# ProDoc_Board2_2025-10-18.net
KiCad netlist of a schematic drawn in EasyEDA Pro
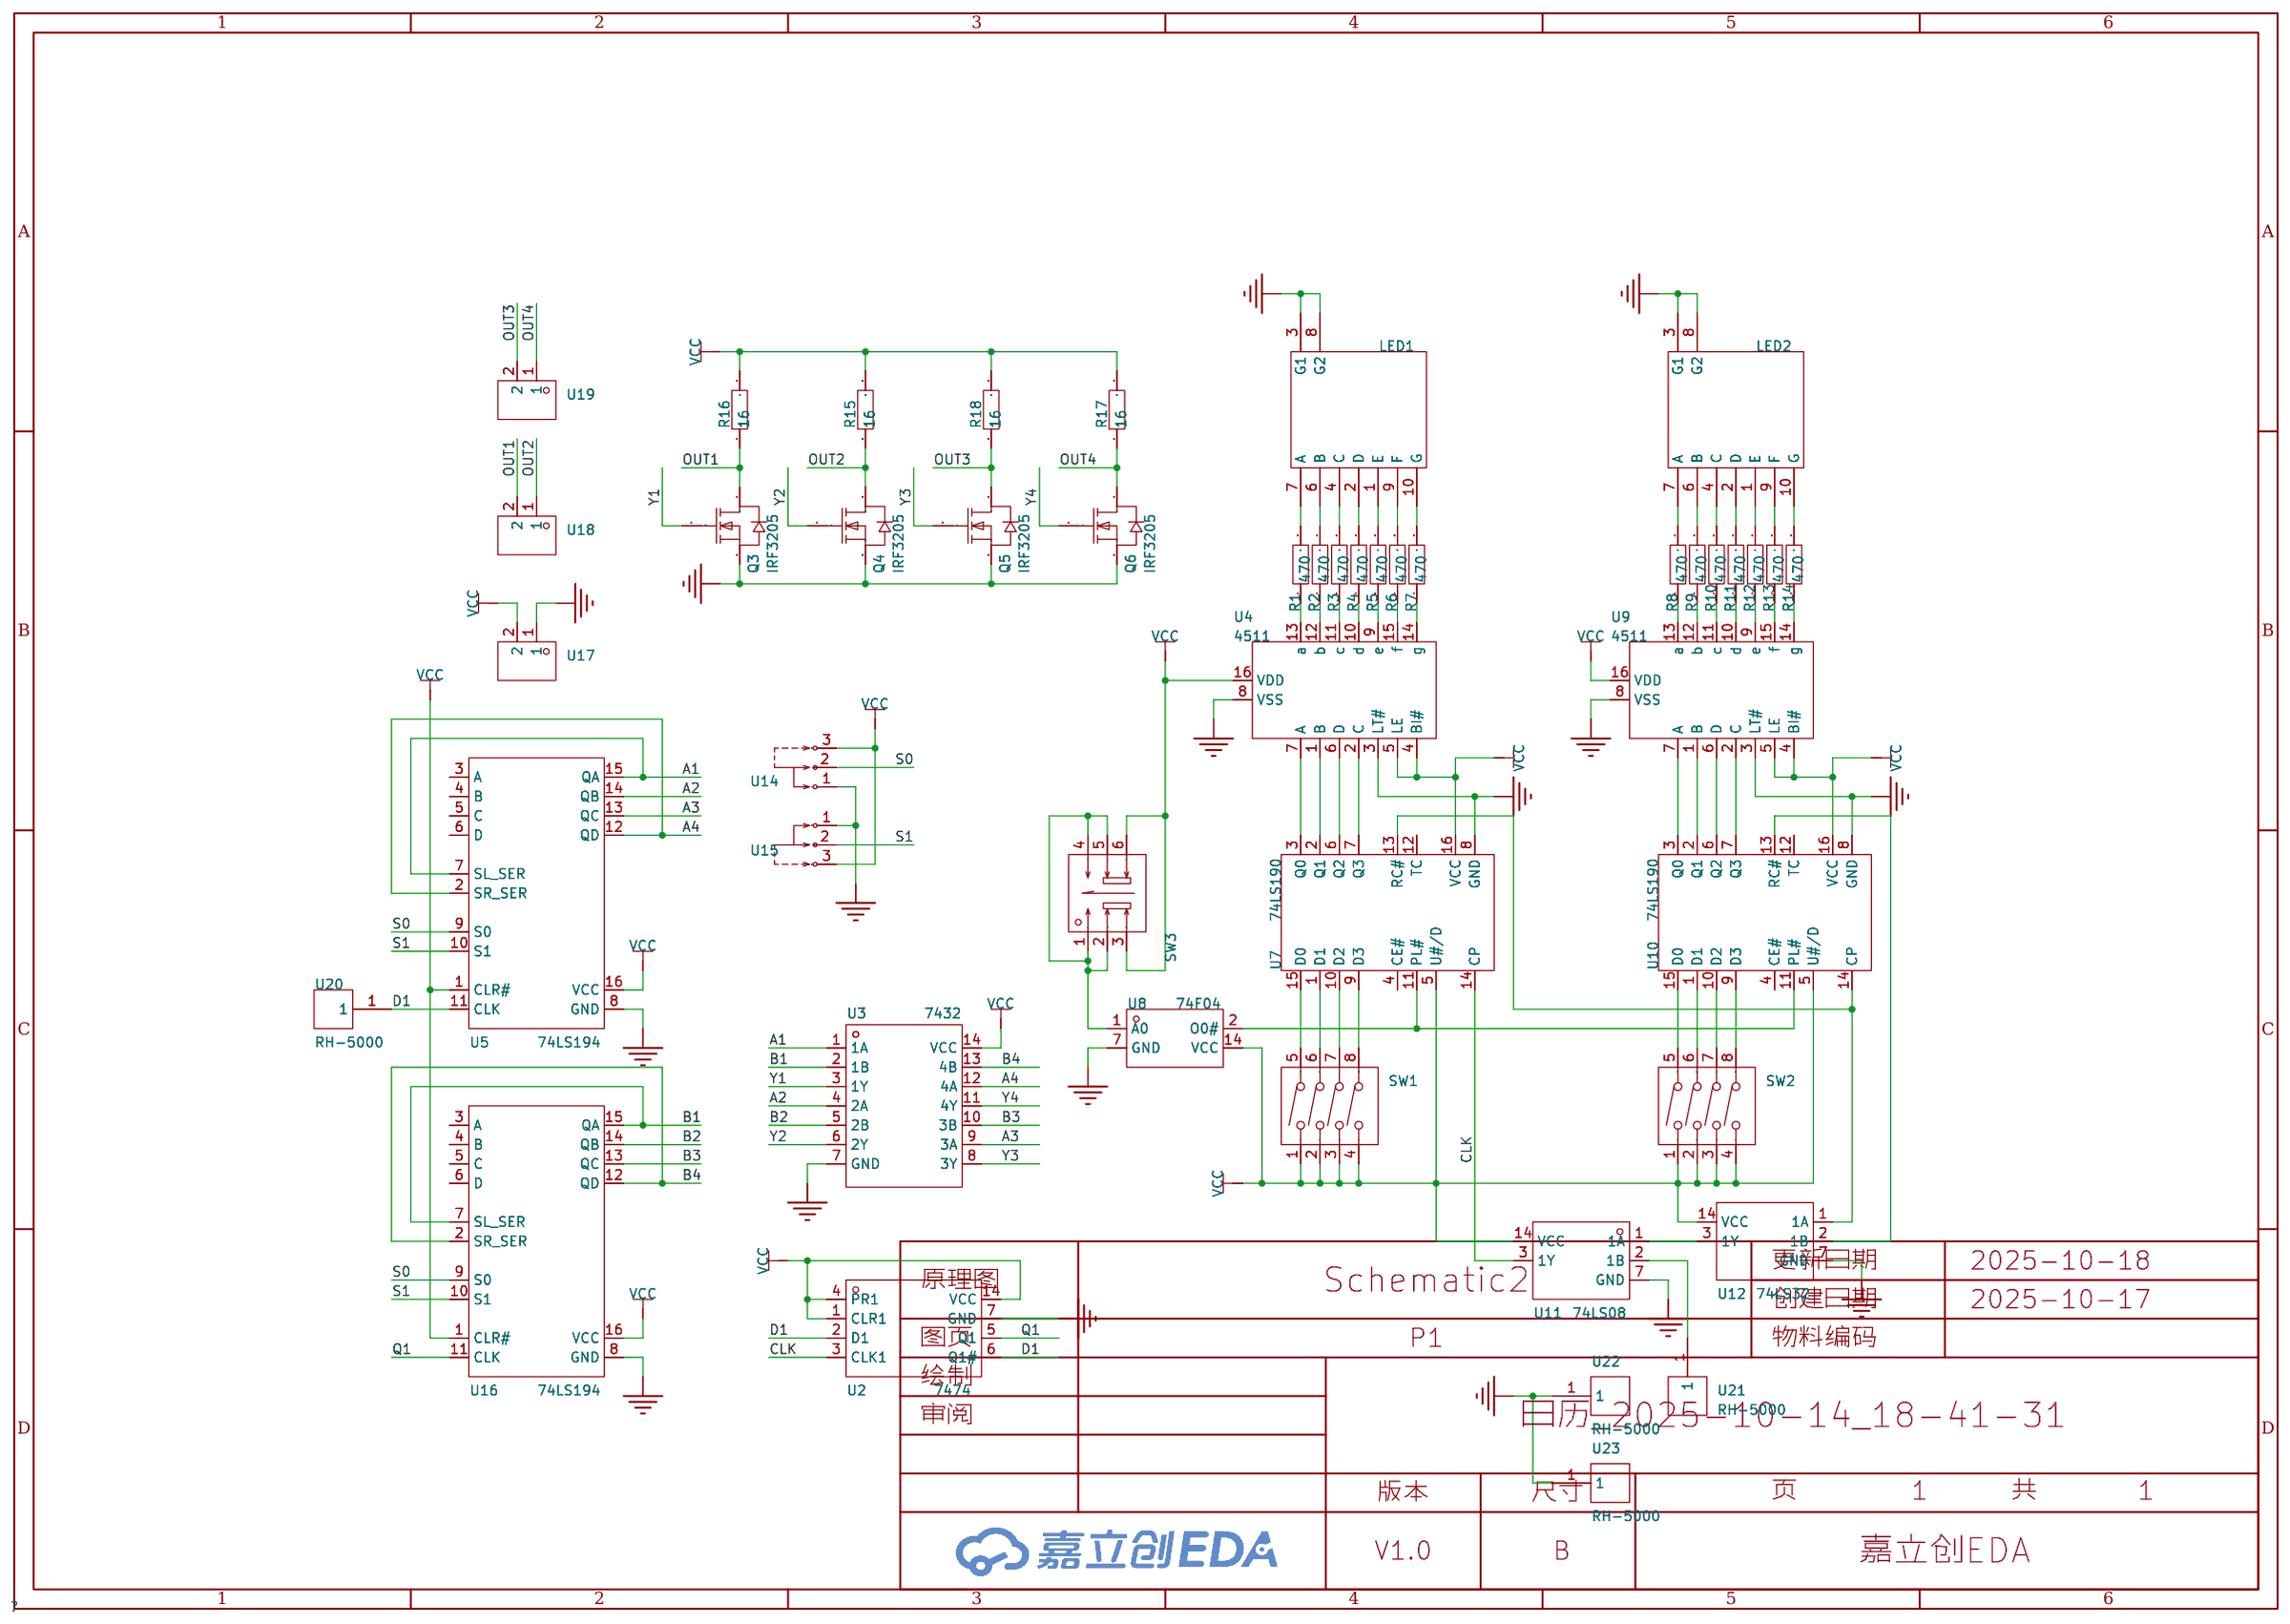
[diagram p0: schematic sheet]

(export (version "E")
  (design (tool "Eeschema 10.0.6"))
  (components
    (comp (ref "LED1")
      (value "FJ5161AH")
      (footprint "easyedapro:LED-SEG-TH_10P-L12.6-W19.0-P2.54-S15.24-BL")
      (description "数码管位数:1位;字符尺寸(英寸):0.56;耗散功率(Pd):-;发光颜色:红色;LED极性:共阴极;")
      (fields (field (name "Manufacturer") "志浩"))
      (libsource (lib "easyedapro") (part "FJ5161AH"))
    )
    (comp (ref "LED2")
      (value "FJ5161AH")
      (footprint "easyedapro:LED-SEG-TH_10P-L12.6-W19.0-P2.54-S15.24-BL")
      (description "数码管位数:1位;字符尺寸(英寸):0.56;耗散功率(Pd):-;发光颜色:红色;LED极性:共阴极;")
      (fields (field (name "Manufacturer") "志浩"))
      (libsource (lib "easyedapro") (part "FJ5161AH"))
    )
    (comp (ref "Q3")
      (value "IRF3205")
      (footprint "easyedapro:TO-220-3_L10.0-W4.5-P2.54-L")
      (fields (field (name "Manufacturer") "Infineon(英飞凌)"))
      (libsource (lib "easyedapro") (part "IRF3205PBF"))
    )
    (comp (ref "Q4")
      (value "IRF3205")
      (footprint "easyedapro:TO-220-3_L10.0-W4.5-P2.54-L")
      (fields (field (name "Manufacturer") "Infineon(英飞凌)"))
      (libsource (lib "easyedapro") (part "IRF3205PBF"))
    )
    (comp (ref "Q5")
      (value "IRF3205")
      (footprint "easyedapro:TO-220-3_L10.0-W4.5-P2.54-L")
      (fields (field (name "Manufacturer") "Infineon(英飞凌)"))
      (libsource (lib "easyedapro") (part "IRF3205PBF"))
    )
    (comp (ref "Q6")
      (value "IRF3205")
      (footprint "easyedapro:TO-220-3_L10.0-W4.5-P2.54-L")
      (fields (field (name "Manufacturer") "Infineon(英飞凌)"))
      (libsource (lib "easyedapro") (part "IRF3205PBF"))
    )
    (comp (ref "R1")
      (value "470")
      (footprint "easyedapro:RES-TH_BD2.5-L6.5-P10.50-D0.6")
      (description "电阻类型:金属膜电阻;阻值:1kΩ;精度:±1%;功率:250mW;温度系数:±50ppm/°C;")
      (fields
        (field (name "Manufacturer Part") "MFR0W4F1001A50")
        (field (name "Manufacturer") "UNI-ROYAL(厚声)")
      )
      (libsource (lib "easyedapro") (part "MFR0W4F1001A50"))
    )
    (comp (ref "R2")
      (value "470")
      (footprint "easyedapro:RES-TH_BD2.5-L6.5-P10.50-D0.6")
      (description "电阻类型:金属膜电阻;阻值:1kΩ;精度:±1%;功率:250mW;温度系数:±50ppm/°C;")
      (fields
        (field (name "Manufacturer Part") "MFR0W4F1001A50")
        (field (name "Manufacturer") "UNI-ROYAL(厚声)")
      )
      (libsource (lib "easyedapro") (part "MFR0W4F1001A50"))
    )
    (comp (ref "R3")
      (value "470")
      (footprint "easyedapro:RES-TH_BD2.5-L6.5-P10.50-D0.6")
      (description "电阻类型:金属膜电阻;阻值:1kΩ;精度:±1%;功率:250mW;温度系数:±50ppm/°C;")
      (fields
        (field (name "Manufacturer Part") "MFR0W4F1001A50")
        (field (name "Manufacturer") "UNI-ROYAL(厚声)")
      )
      (libsource (lib "easyedapro") (part "MFR0W4F1001A50"))
    )
    (comp (ref "R4")
      (value "470")
      (footprint "easyedapro:RES-TH_BD2.5-L6.5-P10.50-D0.6")
      (description "电阻类型:金属膜电阻;阻值:1kΩ;精度:±1%;功率:250mW;温度系数:±50ppm/°C;")
      (fields
        (field (name "Manufacturer Part") "MFR0W4F1001A50")
        (field (name "Manufacturer") "UNI-ROYAL(厚声)")
      )
      (libsource (lib "easyedapro") (part "MFR0W4F1001A50"))
    )
    (comp (ref "R5")
      (value "470")
      (footprint "easyedapro:RES-TH_BD2.5-L6.5-P10.50-D0.6")
      (description "电阻类型:金属膜电阻;阻值:1kΩ;精度:±1%;功率:250mW;温度系数:±50ppm/°C;")
      (fields
        (field (name "Manufacturer Part") "MFR0W4F1001A50")
        (field (name "Manufacturer") "UNI-ROYAL(厚声)")
      )
      (libsource (lib "easyedapro") (part "MFR0W4F1001A50"))
    )
    (comp (ref "R6")
      (value "470")
      (footprint "easyedapro:RES-TH_BD2.5-L6.5-P10.50-D0.6")
      (description "电阻类型:金属膜电阻;阻值:1kΩ;精度:±1%;功率:250mW;温度系数:±50ppm/°C;")
      (fields
        (field (name "Manufacturer Part") "MFR0W4F1001A50")
        (field (name "Manufacturer") "UNI-ROYAL(厚声)")
      )
      (libsource (lib "easyedapro") (part "MFR0W4F1001A50"))
    )
    (comp (ref "R7")
      (value "470")
      (footprint "easyedapro:RES-TH_BD2.5-L6.5-P10.50-D0.6")
      (description "电阻类型:金属膜电阻;阻值:1kΩ;精度:±1%;功率:250mW;温度系数:±50ppm/°C;")
      (fields
        (field (name "Manufacturer Part") "MFR0W4F1001A50")
        (field (name "Manufacturer") "UNI-ROYAL(厚声)")
      )
      (libsource (lib "easyedapro") (part "MFR0W4F1001A50"))
    )
    (comp (ref "R8")
      (value "470")
      (footprint "easyedapro:RES-TH_BD2.5-L6.5-P10.50-D0.6")
      (description "电阻类型:金属膜电阻;阻值:1kΩ;精度:±1%;功率:250mW;温度系数:±50ppm/°C;")
      (fields
        (field (name "Manufacturer Part") "MFR0W4F1001A50")
        (field (name "Manufacturer") "UNI-ROYAL(厚声)")
      )
      (libsource (lib "easyedapro") (part "MFR0W4F1001A50"))
    )
    (comp (ref "R9")
      (value "470")
      (footprint "easyedapro:RES-TH_BD2.5-L6.5-P10.50-D0.6")
      (description "电阻类型:金属膜电阻;阻值:1kΩ;精度:±1%;功率:250mW;温度系数:±50ppm/°C;")
      (fields
        (field (name "Manufacturer Part") "MFR0W4F1001A50")
        (field (name "Manufacturer") "UNI-ROYAL(厚声)")
      )
      (libsource (lib "easyedapro") (part "MFR0W4F1001A50"))
    )
    (comp (ref "R10")
      (value "470")
      (footprint "easyedapro:RES-TH_BD2.5-L6.5-P10.50-D0.6")
      (description "电阻类型:金属膜电阻;阻值:1kΩ;精度:±1%;功率:250mW;温度系数:±50ppm/°C;")
      (fields
        (field (name "Manufacturer Part") "MFR0W4F1001A50")
        (field (name "Manufacturer") "UNI-ROYAL(厚声)")
      )
      (libsource (lib "easyedapro") (part "MFR0W4F1001A50"))
    )
    (comp (ref "R11")
      (value "470")
      (footprint "easyedapro:RES-TH_BD2.5-L6.5-P10.50-D0.6")
      (description "电阻类型:金属膜电阻;阻值:1kΩ;精度:±1%;功率:250mW;温度系数:±50ppm/°C;")
      (fields
        (field (name "Manufacturer Part") "MFR0W4F1001A50")
        (field (name "Manufacturer") "UNI-ROYAL(厚声)")
      )
      (libsource (lib "easyedapro") (part "MFR0W4F1001A50"))
    )
    (comp (ref "R12")
      (value "470")
      (footprint "easyedapro:RES-TH_BD2.5-L6.5-P10.50-D0.6")
      (description "电阻类型:金属膜电阻;阻值:1kΩ;精度:±1%;功率:250mW;温度系数:±50ppm/°C;")
      (fields
        (field (name "Manufacturer Part") "MFR0W4F1001A50")
        (field (name "Manufacturer") "UNI-ROYAL(厚声)")
      )
      (libsource (lib "easyedapro") (part "MFR0W4F1001A50"))
    )
    (comp (ref "R13")
      (value "470")
      (footprint "easyedapro:RES-TH_BD2.5-L6.5-P10.50-D0.6")
      (description "电阻类型:金属膜电阻;阻值:1kΩ;精度:±1%;功率:250mW;温度系数:±50ppm/°C;")
      (fields
        (field (name "Manufacturer Part") "MFR0W4F1001A50")
        (field (name "Manufacturer") "UNI-ROYAL(厚声)")
      )
      (libsource (lib "easyedapro") (part "MFR0W4F1001A50"))
    )
    (comp (ref "R14")
      (value "470")
      (footprint "easyedapro:RES-TH_BD2.5-L6.5-P10.50-D0.6")
      (description "电阻类型:金属膜电阻;阻值:1kΩ;精度:±1%;功率:250mW;温度系数:±50ppm/°C;")
      (fields
        (field (name "Manufacturer Part") "MFR0W4F1001A50")
        (field (name "Manufacturer") "UNI-ROYAL(厚声)")
      )
      (libsource (lib "easyedapro") (part "MFR0W4F1001A50"))
    )
    (comp (ref "R15")
      (value "16")
      (footprint "easyedapro:RES-TH_BD2.5-L6.5-P10.50-D0.6")
      (description "电阻类型:金属膜电阻;阻值:1kΩ;精度:±1%;功率:250mW;温度系数:±50ppm/°C;")
      (fields
        (field (name "Manufacturer Part") "MFR0W4F1001A50")
        (field (name "Manufacturer") "UNI-ROYAL(厚声)")
      )
      (libsource (lib "easyedapro") (part "MFR0W4F1001A50"))
    )
    (comp (ref "R16")
      (value "16")
      (footprint "easyedapro:RES-TH_BD2.5-L6.5-P10.50-D0.6")
      (description "电阻类型:金属膜电阻;阻值:1kΩ;精度:±1%;功率:250mW;温度系数:±50ppm/°C;")
      (fields
        (field (name "Manufacturer Part") "MFR0W4F1001A50")
        (field (name "Manufacturer") "UNI-ROYAL(厚声)")
      )
      (libsource (lib "easyedapro") (part "MFR0W4F1001A50"))
    )
    (comp (ref "R17")
      (value "16")
      (footprint "easyedapro:RES-TH_BD2.5-L6.5-P10.50-D0.6")
      (description "电阻类型:金属膜电阻;阻值:1kΩ;精度:±1%;功率:250mW;温度系数:±50ppm/°C;")
      (fields
        (field (name "Manufacturer Part") "MFR0W4F1001A50")
        (field (name "Manufacturer") "UNI-ROYAL(厚声)")
      )
      (libsource (lib "easyedapro") (part "MFR0W4F1001A50"))
    )
    (comp (ref "R18")
      (value "16")
      (footprint "easyedapro:RES-TH_BD2.5-L6.5-P10.50-D0.6")
      (description "电阻类型:金属膜电阻;阻值:1kΩ;精度:±1%;功率:250mW;温度系数:±50ppm/°C;")
      (fields
        (field (name "Manufacturer Part") "MFR0W4F1001A50")
        (field (name "Manufacturer") "UNI-ROYAL(厚声)")
      )
      (libsource (lib "easyedapro") (part "MFR0W4F1001A50"))
    )
    (comp (ref "SW1")
      (value "DSWB04LHGET")
      (footprint "easyedapro:SW-TH_DSWB04LHGET")
      (description "类型:平拨,凸起式;电路结构:单刀单掷;开关位数:4位;工作寿命:-;颜色:红色;")
      (fields (field (name "Manufacturer") "YE"))
      (libsource (lib "easyedapro") (part "DSWB04LHGET"))
    )
    (comp (ref "SW2")
      (value "DSWB04LHGET")
      (footprint "easyedapro:SW-TH_DSWB04LHGET")
      (description "类型:平拨,凸起式;电路结构:单刀单掷;开关位数:4位;工作寿命:-;颜色:红色;")
      (fields (field (name "Manufacturer") "YE"))
      (libsource (lib "easyedapro") (part "DSWB04LHGET"))
    )
    (comp (ref "SW3")
      (value "5.8 ZSGT")
      (footprint "easyedapro:SW-TH_5.8ZSGT")
      (description "电路结构:双刀双掷;自锁/无锁:自锁;安装方式:直插;触点电流:110mA;额定电压:30V;带灯:不带;作用力:1.5N;工作寿命:10万次;")
      (fields (field (name "Manufacturer") "SHOU HAN(首韩)"))
      (libsource (lib "easyedapro") (part "5.8 ZSGT"))
    )
    (comp (ref "U2")
      (value "7474")
      (footprint "easyedapro:PDIP-14_L19.5-W6.7-P2.54-LS7.9-BL")
      (description "类型:D-型;电源电压:4.75V~5.25V;时钟频率:15MHz;元件数:2;每个元件位数:1;最大传播延迟:40ns@5V,15pF;静态电流(Iq):30mA;")
      (fields (field (name "Manufacturer") "TI(德州仪器)"))
      (libsource (lib "easyedapro") (part "DM7474N"))
    )
    (comp (ref "U3")
      (value "7432")
      (footprint "easyedapro:PDIP-14_L19.3-W6.4-P2.54-LS7.6-BL")
      (description "逻辑类型:或门;通道数:4;电源电压:4.75V~5.25V;静态电流(最大值):22mA;最大传播延迟:22ns@5V,15pF;")
      (fields (field (name "Manufacturer") "TI(德州仪器)"))
      (libsource (lib "easyedapro") (part "SN7432N"))
    )
    (comp (ref "U4")
      (value "4511")
      (description "工作电压:-;灌电流(IOL):-;拉电流(IOH):-;")
      (fields (field (name "Manufacturer") "HGC(深圳汉芯)"))
      (libsource (lib "easyedapro") (part "CD4511BE"))
    )
    (comp (ref "U5")
      (value "74LS194")
      (footprint "easyedapro:DIP-16_L19.2-W6.6-P2.54-LS7.6-BL")
      (description "功能:-;")
      (fields (field (name "Manufacturer") "XINLUDA(信路达)"))
      (libsource (lib "easyedapro") (part "XD74LS194"))
    )
    (comp (ref "U7")
      (value "74LS190")
      (footprint "easyedapro:PDIP-16_L19.2-W6.6-P2.54-LS7.6-BL")
      (description "工作电压:-;元件数:1;触发沿:-;计数速率:28MHz;")
      (fields (field (name "Manufacturer") "XBLW(芯伯乐)"))
      (libsource (lib "easyedapro") (part "SN74LS190N(XBLW)"))
    )
    (comp (ref "U8")
      (value "74F04")
      (footprint "easyedapro:PDIP-14_L19.3-W6.4-P2.54-LS7.9-BL-1")
      (description "电源电压:4.5V~5.5V;供电电流(最大值):15.3mA;电路数:6;最大传播延迟(tpd):5ns@5V,50pF;")
      (fields (field (name "Manufacturer") "TI(德州仪器)"))
      (libsource (lib "easyedapro") (part "74F04PC_C3272304"))
    )
    (comp (ref "U9")
      (value "4511")
      (description "工作电压:-;灌电流(IOL):-;拉电流(IOH):-;")
      (fields (field (name "Manufacturer") "HGC(深圳汉芯)"))
      (libsource (lib "easyedapro") (part "CD4511BE"))
    )
    (comp (ref "U10")
      (value "74LS190")
      (footprint "easyedapro:PDIP-16_L19.2-W6.6-P2.54-LS7.6-BL")
      (description "工作电压:-;元件数:1;触发沿:-;计数速率:28MHz;")
      (fields (field (name "Manufacturer") "XBLW(芯伯乐)"))
      (libsource (lib "easyedapro") (part "SN74LS190N(XBLW)"))
    )
    (comp (ref "U11")
      (value "74LS08")
      (footprint "easyedapro:PDIP-14_L19.3-W6.4-P2.54-LS7.9-BL-1")
      (description "逻辑类型:与门;通道数:4;工作电压:4.75V~5.25V;传播延迟(tpd):-;")
      (fields (field (name "Manufacturer") "TI(德州仪器)"))
      (libsource (lib "easyedapro") (part "SN74LS08N"))
    )
    (comp (ref "U12")
      (value "74LS32")
      (footprint "easyedapro:DIP-14_L19.1-W6.4-P2.54-LS7.6-BL")
      (description "逻辑类型:或门;通道数:4;工作电压:2V~6V;静态电流(Iq):2uA;传播延迟(tpd):15ns@6V,15pF;")
      (fields (field (name "Manufacturer") "LX(灵星芯微)"))
      (libsource (lib "easyedapro") (part "SN74LS32N_C22466295"))
    )
    (comp (ref "U14")
      (value "SS12D10G5")
      (footprint "easyedapro:SW-TH_SHOU-HAN_SS12D10G4")
      (description "电路结构:单刀双掷;安装方式:直插;额定电流:2A;额定电压:125V;工作寿命:3千次;")
      (fields (field (name "Manufacturer") "SHOU HAN(首韩)"))
      (libsource (lib "easyedapro") (part "SS12D10G5"))
    )
    (comp (ref "U15")
      (value "SS12D10G5")
      (footprint "easyedapro:SW-TH_SHOU-HAN_SS12D10G4")
      (description "电路结构:单刀双掷;安装方式:直插;额定电流:2A;额定电压:125V;工作寿命:3千次;")
      (fields (field (name "Manufacturer") "SHOU HAN(首韩)"))
      (libsource (lib "easyedapro") (part "SS12D10G5"))
    )
    (comp (ref "U16")
      (value "74LS194")
      (footprint "easyedapro:DIP-16_L19.2-W6.6-P2.54-LS7.6-BL")
      (description "功能:-;")
      (fields (field (name "Manufacturer") "XINLUDA(信路达)"))
      (libsource (lib "easyedapro") (part "XD74LS194"))
    )
    (comp (ref "U17")
      (value "DB301V-3.5-2P-GN-S")
      (footprint "easyedapro:CONN-TH_DB301V-3.5-2P-GN")
      (fields (field (name "Manufacturer") "DORABO(地博电气)"))
      (libsource (lib "easyedapro") (part "DB301V-3.5-2P-GN"))
    )
    (comp (ref "U18")
      (value "DB301V-3.5-2P-GN-S")
      (footprint "easyedapro:CONN-TH_DB301V-3.5-2P-GN")
      (fields (field (name "Manufacturer") "DORABO(地博电气)"))
      (libsource (lib "easyedapro") (part "DB301V-3.5-2P-GN"))
    )
    (comp (ref "U19")
      (value "DB301V-3.5-2P-GN-S")
      (footprint "easyedapro:CONN-TH_DB301V-3.5-2P-GN")
      (fields (field (name "Manufacturer") "DORABO(地博电气)"))
      (libsource (lib "easyedapro") (part "DB301V-3.5-2P-GN"))
    )
    (comp (ref "U20")
      (value "RH-5000")
      (footprint "easyedapro:TEST-TH_BD2.54-P1.4_RED")
      (fields (field (name "Manufacturer") "荣和"))
      (libsource (lib "easyedapro") (part "RH-5000"))
    )
    (comp (ref "U21")
      (value "RH-5000")
      (footprint "easyedapro:TEST-TH_BD2.54-P1.4_RED")
      (fields (field (name "Manufacturer") "荣和"))
      (libsource (lib "easyedapro") (part "RH-5000"))
    )
    (comp (ref "U22")
      (value "RH-5000")
      (footprint "easyedapro:TEST-TH_BD2.54-P1.4_RED")
      (fields (field (name "Manufacturer") "荣和"))
      (libsource (lib "easyedapro") (part "RH-5000"))
    )
    (comp (ref "U23")
      (value "RH-5000")
      (footprint "easyedapro:TEST-TH_BD2.54-P1.4_RED")
      (fields (field (name "Manufacturer") "荣和"))
      (libsource (lib "easyedapro") (part "RH-5000"))
    )
  )
  (nets
    (net (code "1") (name "/A1") (class "Default")
      (node (ref "U3") (pin "1") (pinfunction "1A_1") (pintype "unspecified"))
      (node (ref "U5") (pin "15") (pinfunction "QA_15") (pintype "unspecified"))
      (node (ref "U5") (pin "7") (pinfunction "SL_SER_7") (pintype "unspecified"))
    )
    (net (code "2") (name "/A2") (class "Default")
      (node (ref "U3") (pin "4") (pinfunction "2A_4") (pintype "unspecified"))
      (node (ref "U5") (pin "14") (pinfunction "QB_14") (pintype "unspecified"))
    )
    (net (code "3") (name "/A3") (class "Default")
      (node (ref "U3") (pin "9") (pinfunction "3A_9") (pintype "unspecified"))
      (node (ref "U5") (pin "13") (pinfunction "QC_13") (pintype "unspecified"))
    )
    (net (code "4") (name "/A4") (class "Default")
      (node (ref "U3") (pin "12") (pinfunction "4A_12") (pintype "unspecified"))
      (node (ref "U5") (pin "12") (pinfunction "QD_12") (pintype "unspecified"))
      (node (ref "U5") (pin "2") (pinfunction "SR_SER_2") (pintype "unspecified"))
    )
    (net (code "5") (name "/B1") (class "Default")
      (node (ref "U16") (pin "15") (pinfunction "QA_15") (pintype "unspecified"))
      (node (ref "U16") (pin "7") (pinfunction "SL_SER_7") (pintype "unspecified"))
      (node (ref "U3") (pin "2") (pinfunction "1B_2") (pintype "unspecified"))
    )
    (net (code "6") (name "/B2") (class "Default")
      (node (ref "U16") (pin "14") (pinfunction "QB_14") (pintype "unspecified"))
      (node (ref "U3") (pin "5") (pinfunction "2B_5") (pintype "unspecified"))
    )
    (net (code "7") (name "/B3") (class "Default")
      (node (ref "U16") (pin "13") (pinfunction "QC_13") (pintype "unspecified"))
      (node (ref "U3") (pin "10") (pinfunction "3B_10") (pintype "unspecified"))
    )
    (net (code "8") (name "/B4") (class "Default")
      (node (ref "U16") (pin "12") (pinfunction "QD_12") (pintype "unspecified"))
      (node (ref "U16") (pin "2") (pinfunction "SR_SER_2") (pintype "unspecified"))
      (node (ref "U3") (pin "13") (pinfunction "4B_13") (pintype "unspecified"))
    )
    (net (code "9") (name "/CLK") (class "Default")
      (node (ref "U11") (pin "3") (pinfunction "1Y_3") (pintype "unspecified"))
      (node (ref "U2") (pin "3") (pinfunction "CLK1_3") (pintype "unspecified"))
      (node (ref "U7") (pin "14") (pinfunction "CP_14") (pintype "unspecified"))
    )
    (net (code "10") (name "/D1") (class "Default")
      (node (ref "U2") (pin "2") (pinfunction "D1_2") (pintype "unspecified"))
      (node (ref "U2") (pin "6") (pinfunction "Q1#_6") (pintype "unspecified"))
      (node (ref "U20") (pin "1") (pinfunction "1_1") (pintype "unspecified"))
      (node (ref "U5") (pin "11") (pinfunction "CLK_11") (pintype "unspecified"))
    )
    (net (code "11") (name "/OUT1") (class "Default")
      (node (ref "Q3") (pin "2") (pinfunction "D_2") (pintype "unspecified"))
      (node (ref "R16") (pin "1") (pinfunction "1_1") (pintype "input"))
      (node (ref "U18") (pin "2") (pinfunction "2_2") (pintype "unspecified"))
    )
    (net (code "12") (name "/OUT2") (class "Default")
      (node (ref "Q4") (pin "2") (pinfunction "D_2") (pintype "unspecified"))
      (node (ref "R15") (pin "1") (pinfunction "1_1") (pintype "input"))
      (node (ref "U18") (pin "1") (pinfunction "1_1") (pintype "unspecified"))
    )
    (net (code "13") (name "/OUT3") (class "Default")
      (node (ref "Q5") (pin "2") (pinfunction "D_2") (pintype "unspecified"))
      (node (ref "R18") (pin "1") (pinfunction "1_1") (pintype "input"))
      (node (ref "U19") (pin "2") (pinfunction "2_2") (pintype "unspecified"))
    )
    (net (code "14") (name "/OUT4") (class "Default")
      (node (ref "Q6") (pin "2") (pinfunction "D_2") (pintype "unspecified"))
      (node (ref "R17") (pin "1") (pinfunction "1_1") (pintype "input"))
      (node (ref "U19") (pin "1") (pinfunction "1_1") (pintype "unspecified"))
    )
    (net (code "15") (name "/Q1") (class "Default")
      (node (ref "U16") (pin "11") (pinfunction "CLK_11") (pintype "unspecified"))
      (node (ref "U2") (pin "5") (pinfunction "Q1_5") (pintype "unspecified"))
    )
    (net (code "16") (name "/S0") (class "Default")
      (node (ref "U14") (pin "2") (pinfunction "2_2") (pintype "unspecified"))
      (node (ref "U16") (pin "9") (pinfunction "S0_9") (pintype "unspecified"))
      (node (ref "U5") (pin "9") (pinfunction "S0_9") (pintype "unspecified"))
    )
    (net (code "17") (name "/S1") (class "Default")
      (node (ref "U15") (pin "2") (pinfunction "2_2") (pintype "unspecified"))
      (node (ref "U16") (pin "10") (pinfunction "S1_10") (pintype "unspecified"))
      (node (ref "U5") (pin "10") (pinfunction "S1_10") (pintype "unspecified"))
    )
    (net (code "18") (name "/Y1") (class "Default")
      (node (ref "Q3") (pin "1") (pinfunction "G_1") (pintype "unspecified"))
      (node (ref "U3") (pin "3") (pinfunction "1Y_3") (pintype "unspecified"))
    )
    (net (code "19") (name "/Y2") (class "Default")
      (node (ref "Q4") (pin "1") (pinfunction "G_1") (pintype "unspecified"))
      (node (ref "U3") (pin "6") (pinfunction "2Y_6") (pintype "unspecified"))
    )
    (net (code "20") (name "/Y3") (class "Default")
      (node (ref "Q5") (pin "1") (pinfunction "G_1") (pintype "unspecified"))
      (node (ref "U3") (pin "8") (pinfunction "3Y_8") (pintype "unspecified"))
    )
    (net (code "21") (name "/Y4") (class "Default")
      (node (ref "Q6") (pin "1") (pinfunction "G_1") (pintype "unspecified"))
      (node (ref "U3") (pin "11") (pinfunction "4Y_11") (pintype "unspecified"))
    )
    (net (code "22") (name "GND") (class "Default")
      (node (ref "LED1") (pin "3") (pinfunction "G1_3") (pintype "input"))
      (node (ref "LED1") (pin "8") (pinfunction "G2_8") (pintype "input"))
      (node (ref "LED2") (pin "3") (pinfunction "G1_3") (pintype "input"))
      (node (ref "LED2") (pin "8") (pinfunction "G2_8") (pintype "input"))
      (node (ref "Q3") (pin "3") (pinfunction "S_3") (pintype "unspecified"))
      (node (ref "Q4") (pin "3") (pinfunction "S_3") (pintype "unspecified"))
      (node (ref "Q5") (pin "3") (pinfunction "S_3") (pintype "unspecified"))
      (node (ref "Q6") (pin "3") (pinfunction "S_3") (pintype "unspecified"))
      (node (ref "U10") (pin "8") (pinfunction "GND_8") (pintype "unspecified"))
      (node (ref "U11") (pin "7") (pinfunction "GND_7") (pintype "unspecified"))
      (node (ref "U12") (pin "7") (pinfunction "GND_7") (pintype "unspecified"))
      (node (ref "U14") (pin "1") (pinfunction "1_1") (pintype "unspecified"))
      (node (ref "U15") (pin "1") (pinfunction "1_1") (pintype "unspecified"))
      (node (ref "U16") (pin "8") (pinfunction "GND_8") (pintype "unspecified"))
      (node (ref "U17") (pin "1") (pinfunction "1_1") (pintype "unspecified"))
      (node (ref "U2") (pin "7") (pinfunction "GND_7") (pintype "unspecified"))
      (node (ref "U22") (pin "1") (pinfunction "1_1") (pintype "unspecified"))
      (node (ref "U23") (pin "1") (pinfunction "1_1") (pintype "unspecified"))
      (node (ref "U3") (pin "7") (pinfunction "GND_7") (pintype "unspecified"))
      (node (ref "U4") (pin "3") (pinfunction "LT#_3") (pintype "unspecified"))
      (node (ref "U4") (pin "8") (pinfunction "VSS_8") (pintype "unspecified"))
      (node (ref "U5") (pin "8") (pinfunction "GND_8") (pintype "unspecified"))
      (node (ref "U7") (pin "8") (pinfunction "GND_8") (pintype "unspecified"))
      (node (ref "U8") (pin "7") (pinfunction "GND_7") (pintype "unspecified"))
      (node (ref "U9") (pin "3") (pinfunction "LT#_3") (pintype "unspecified"))
      (node (ref "U9") (pin "8") (pinfunction "VSS_8") (pintype "unspecified"))
    )
    (net (code "23") (name "Net-(LED1-A)") (class "Default")
      (node (ref "LED1") (pin "7") (pinfunction "A_7") (pintype "input"))
      (node (ref "R1") (pin "2") (pinfunction "2_2") (pintype "input"))
    )
    (net (code "24") (name "Net-(LED1-B)") (class "Default")
      (node (ref "LED1") (pin "6") (pinfunction "B_6") (pintype "input"))
      (node (ref "R2") (pin "2") (pinfunction "2_2") (pintype "input"))
    )
    (net (code "25") (name "Net-(LED1-C)") (class "Default")
      (node (ref "LED1") (pin "4") (pinfunction "C_4") (pintype "input"))
      (node (ref "R3") (pin "2") (pinfunction "2_2") (pintype "input"))
    )
    (net (code "26") (name "Net-(LED1-D)") (class "Default")
      (node (ref "LED1") (pin "2") (pinfunction "D_2") (pintype "input"))
      (node (ref "R4") (pin "2") (pinfunction "2_2") (pintype "input"))
    )
    (net (code "27") (name "Net-(LED1-E)") (class "Default")
      (node (ref "LED1") (pin "1") (pinfunction "E_1") (pintype "input"))
      (node (ref "R5") (pin "2") (pinfunction "2_2") (pintype "input"))
    )
    (net (code "28") (name "Net-(LED1-F)") (class "Default")
      (node (ref "LED1") (pin "9") (pinfunction "F_9") (pintype "input"))
      (node (ref "R6") (pin "2") (pinfunction "2_2") (pintype "input"))
    )
    (net (code "29") (name "Net-(LED1-G)") (class "Default")
      (node (ref "LED1") (pin "10") (pinfunction "G_10") (pintype "input"))
      (node (ref "R7") (pin "2") (pinfunction "2_2") (pintype "input"))
    )
    (net (code "30") (name "Net-(LED2-A)") (class "Default")
      (node (ref "LED2") (pin "7") (pinfunction "A_7") (pintype "input"))
      (node (ref "R8") (pin "2") (pinfunction "2_2") (pintype "input"))
    )
    (net (code "31") (name "Net-(LED2-B)") (class "Default")
      (node (ref "LED2") (pin "6") (pinfunction "B_6") (pintype "input"))
      (node (ref "R9") (pin "2") (pinfunction "2_2") (pintype "input"))
    )
    (net (code "32") (name "Net-(LED2-C)") (class "Default")
      (node (ref "LED2") (pin "4") (pinfunction "C_4") (pintype "input"))
      (node (ref "R10") (pin "2") (pinfunction "2_2") (pintype "input"))
    )
    (net (code "33") (name "Net-(LED2-D)") (class "Default")
      (node (ref "LED2") (pin "2") (pinfunction "D_2") (pintype "input"))
      (node (ref "R11") (pin "2") (pinfunction "2_2") (pintype "input"))
    )
    (net (code "34") (name "Net-(LED2-E)") (class "Default")
      (node (ref "LED2") (pin "1") (pinfunction "E_1") (pintype "input"))
      (node (ref "R12") (pin "2") (pinfunction "2_2") (pintype "input"))
    )
    (net (code "35") (name "Net-(LED2-F)") (class "Default")
      (node (ref "LED2") (pin "9") (pinfunction "F_9") (pintype "input"))
      (node (ref "R13") (pin "2") (pinfunction "2_2") (pintype "input"))
    )
    (net (code "36") (name "Net-(LED2-G)") (class "Default")
      (node (ref "LED2") (pin "10") (pinfunction "G_10") (pintype "input"))
      (node (ref "R14") (pin "2") (pinfunction "2_2") (pintype "input"))
    )
    (net (code "37") (name "Net-(U4-A)") (class "Default")
      (node (ref "U4") (pin "7") (pinfunction "A_7") (pintype "unspecified"))
      (node (ref "U7") (pin "3") (pinfunction "Q0_3") (pintype "unspecified"))
    )
    (net (code "38") (name "Net-(U4-B)") (class "Default")
      (node (ref "U4") (pin "1") (pinfunction "B_1") (pintype "unspecified"))
      (node (ref "U7") (pin "2") (pinfunction "Q1_2") (pintype "unspecified"))
    )
    (net (code "39") (name "Net-(U4-C)") (class "Default")
      (node (ref "U4") (pin "2") (pinfunction "C_2") (pintype "unspecified"))
      (node (ref "U7") (pin "7") (pinfunction "Q3_7") (pintype "unspecified"))
    )
    (net (code "40") (name "Net-(U4-D)") (class "Default")
      (node (ref "U4") (pin "6") (pinfunction "D_6") (pintype "unspecified"))
      (node (ref "U7") (pin "6") (pinfunction "Q2_6") (pintype "unspecified"))
    )
    (net (code "41") (name "Net-(U4-a)") (class "Default")
      (node (ref "R1") (pin "1") (pinfunction "1_1") (pintype "input"))
      (node (ref "U4") (pin "13") (pinfunction "a_13") (pintype "unspecified"))
    )
    (net (code "42") (name "Net-(U4-b)") (class "Default")
      (node (ref "R2") (pin "1") (pinfunction "1_1") (pintype "input"))
      (node (ref "U4") (pin "12") (pinfunction "b_12") (pintype "unspecified"))
    )
    (net (code "43") (name "Net-(U4-c)") (class "Default")
      (node (ref "R3") (pin "1") (pinfunction "1_1") (pintype "input"))
      (node (ref "U4") (pin "11") (pinfunction "c_11") (pintype "unspecified"))
    )
    (net (code "44") (name "Net-(U4-d)") (class "Default")
      (node (ref "R4") (pin "1") (pinfunction "1_1") (pintype "input"))
      (node (ref "U4") (pin "10") (pinfunction "d_10") (pintype "unspecified"))
    )
    (net (code "45") (name "Net-(U4-e)") (class "Default")
      (node (ref "R5") (pin "1") (pinfunction "1_1") (pintype "input"))
      (node (ref "U4") (pin "9") (pinfunction "e_9") (pintype "unspecified"))
    )
    (net (code "46") (name "Net-(U4-f)") (class "Default")
      (node (ref "R6") (pin "1") (pinfunction "1_1") (pintype "input"))
      (node (ref "U4") (pin "15") (pinfunction "f_15") (pintype "unspecified"))
    )
    (net (code "47") (name "Net-(U4-g)") (class "Default")
      (node (ref "R7") (pin "1") (pinfunction "1_1") (pintype "input"))
      (node (ref "U4") (pin "14") (pinfunction "g_14") (pintype "unspecified"))
    )
    (net (code "48") (name "Net-(U7-D0)") (class "Default")
      (node (ref "SW1") (pin "5") (pinfunction "5_5") (pintype "unspecified"))
      (node (ref "U7") (pin "15") (pinfunction "D0_15") (pintype "unspecified"))
    )
    (net (code "49") (name "Net-(U7-D1)") (class "Default")
      (node (ref "SW1") (pin "6") (pinfunction "6_6") (pintype "unspecified"))
      (node (ref "U7") (pin "1") (pinfunction "D1_1") (pintype "unspecified"))
    )
    (net (code "50") (name "Net-(U7-D2)") (class "Default")
      (node (ref "SW1") (pin "7") (pinfunction "7_7") (pintype "unspecified"))
      (node (ref "U7") (pin "10") (pinfunction "D2_10") (pintype "unspecified"))
    )
    (net (code "51") (name "Net-(U7-D3)") (class "Default")
      (node (ref "SW1") (pin "8") (pinfunction "8_8") (pintype "unspecified"))
      (node (ref "U7") (pin "9") (pinfunction "D3_9") (pintype "unspecified"))
    )
    (net (code "52") (name "Net-(U8-A0)") (class "Default")
      (node (ref "SW3") (pin "1") (pinfunction "1_1") (pintype "unspecified"))
      (node (ref "SW3") (pin "2") (pinfunction "2_2") (pintype "unspecified"))
      (node (ref "SW3") (pin "4") (pinfunction "4_4") (pintype "unspecified"))
      (node (ref "SW3") (pin "5") (pinfunction "5_5") (pintype "unspecified"))
      (node (ref "U8") (pin "1") (pinfunction "A0_1") (pintype "unspecified"))
    )
    (net (code "53") (name "Net-(U9-a)") (class "Default")
      (node (ref "R8") (pin "1") (pinfunction "1_1") (pintype "input"))
      (node (ref "U9") (pin "13") (pinfunction "a_13") (pintype "unspecified"))
    )
    (net (code "54") (name "Net-(U9-b)") (class "Default")
      (node (ref "R9") (pin "1") (pinfunction "1_1") (pintype "input"))
      (node (ref "U9") (pin "12") (pinfunction "b_12") (pintype "unspecified"))
    )
    (net (code "55") (name "Net-(U9-c)") (class "Default")
      (node (ref "R10") (pin "1") (pinfunction "1_1") (pintype "input"))
      (node (ref "U9") (pin "11") (pinfunction "c_11") (pintype "unspecified"))
    )
    (net (code "56") (name "Net-(U9-d)") (class "Default")
      (node (ref "R11") (pin "1") (pinfunction "1_1") (pintype "input"))
      (node (ref "U9") (pin "10") (pinfunction "d_10") (pintype "unspecified"))
    )
    (net (code "57") (name "Net-(U9-e)") (class "Default")
      (node (ref "R12") (pin "1") (pinfunction "1_1") (pintype "input"))
      (node (ref "U9") (pin "9") (pinfunction "e_9") (pintype "unspecified"))
    )
    (net (code "58") (name "Net-(U9-f)") (class "Default")
      (node (ref "R13") (pin "1") (pinfunction "1_1") (pintype "input"))
      (node (ref "U9") (pin "15") (pinfunction "f_15") (pintype "unspecified"))
    )
    (net (code "59") (name "Net-(U9-g)") (class "Default")
      (node (ref "R14") (pin "1") (pinfunction "1_1") (pintype "input"))
      (node (ref "U9") (pin "14") (pinfunction "g_14") (pintype "unspecified"))
    )
    (net (code "60") (name "Net-(U10-CP)") (class "Default")
      (node (ref "U10") (pin "14") (pinfunction "CP_14") (pintype "unspecified"))
      (node (ref "U12") (pin "1") (pinfunction "1A_1") (pintype "unspecified"))
      (node (ref "U7") (pin "13") (pinfunction "RC#_13") (pintype "unspecified"))
    )
    (net (code "61") (name "Net-(U10-D0)") (class "Default")
      (node (ref "SW2") (pin "5") (pinfunction "5_5") (pintype "unspecified"))
      (node (ref "U10") (pin "15") (pinfunction "D0_15") (pintype "unspecified"))
    )
    (net (code "62") (name "Net-(U10-D1)") (class "Default")
      (node (ref "SW2") (pin "6") (pinfunction "6_6") (pintype "unspecified"))
      (node (ref "U10") (pin "1") (pinfunction "D1_1") (pintype "unspecified"))
    )
    (net (code "63") (name "Net-(U10-D2)") (class "Default")
      (node (ref "SW2") (pin "7") (pinfunction "7_7") (pintype "unspecified"))
      (node (ref "U10") (pin "10") (pinfunction "D2_10") (pintype "unspecified"))
    )
    (net (code "64") (name "Net-(U10-D3)") (class "Default")
      (node (ref "SW2") (pin "8") (pinfunction "8_8") (pintype "unspecified"))
      (node (ref "U10") (pin "9") (pinfunction "D3_9") (pintype "unspecified"))
    )
    (net (code "65") (name "Net-(U10-PL#)") (class "Default")
      (node (ref "U10") (pin "11") (pinfunction "PL#_11") (pintype "unspecified"))
      (node (ref "U7") (pin "11") (pinfunction "PL#_11") (pintype "unspecified"))
      (node (ref "U8") (pin "2") (pinfunction "O0#_2") (pintype "unspecified"))
    )
    (net (code "66") (name "Net-(U10-Q0)") (class "Default")
      (node (ref "U10") (pin "3") (pinfunction "Q0_3") (pintype "unspecified"))
      (node (ref "U9") (pin "7") (pinfunction "A_7") (pintype "unspecified"))
    )
    (net (code "67") (name "Net-(U10-Q1)") (class "Default")
      (node (ref "U10") (pin "2") (pinfunction "Q1_2") (pintype "unspecified"))
      (node (ref "U9") (pin "1") (pinfunction "B_1") (pintype "unspecified"))
    )
    (net (code "68") (name "Net-(U10-Q2)") (class "Default")
      (node (ref "U10") (pin "6") (pinfunction "Q2_6") (pintype "unspecified"))
      (node (ref "U9") (pin "6") (pinfunction "D_6") (pintype "unspecified"))
    )
    (net (code "69") (name "Net-(U10-Q3)") (class "Default")
      (node (ref "U10") (pin "7") (pinfunction "Q3_7") (pintype "unspecified"))
      (node (ref "U9") (pin "2") (pinfunction "C_2") (pintype "unspecified"))
    )
    (net (code "70") (name "Net-(U10-RC#)") (class "Default")
      (node (ref "U10") (pin "13") (pinfunction "RC#_13") (pintype "unspecified"))
      (node (ref "U12") (pin "2") (pinfunction "1B_2") (pintype "unspecified"))
    )
    (net (code "71") (name "Net-(U11-1A)") (class "Default")
      (node (ref "U11") (pin "1") (pinfunction "1A_1") (pintype "unspecified"))
      (node (ref "U12") (pin "3") (pinfunction "1Y_3") (pintype "unspecified"))
    )
    (net (code "72") (name "Net-(U11-1B)") (class "Default")
      (node (ref "U11") (pin "2") (pinfunction "1B_2") (pintype "unspecified"))
      (node (ref "U21") (pin "1") (pinfunction "1_1") (pintype "unspecified"))
    )
    (net (code "73") (name "VCC") (class "Default")
      (node (ref "R15") (pin "2") (pinfunction "2_2") (pintype "input"))
      (node (ref "R16") (pin "2") (pinfunction "2_2") (pintype "input"))
      (node (ref "R17") (pin "2") (pinfunction "2_2") (pintype "input"))
      (node (ref "R18") (pin "2") (pinfunction "2_2") (pintype "input"))
      (node (ref "SW1") (pin "1") (pinfunction "1_1") (pintype "unspecified"))
      (node (ref "SW1") (pin "2") (pinfunction "2_2") (pintype "unspecified"))
      (node (ref "SW1") (pin "3") (pinfunction "3_3") (pintype "unspecified"))
      (node (ref "SW1") (pin "4") (pinfunction "4_4") (pintype "unspecified"))
      (node (ref "SW2") (pin "1") (pinfunction "1_1") (pintype "unspecified"))
      (node (ref "SW2") (pin "2") (pinfunction "2_2") (pintype "unspecified"))
      (node (ref "SW2") (pin "3") (pinfunction "3_3") (pintype "unspecified"))
      (node (ref "SW2") (pin "4") (pinfunction "4_4") (pintype "unspecified"))
      (node (ref "SW3") (pin "3") (pinfunction "3_3") (pintype "unspecified"))
      (node (ref "SW3") (pin "6") (pinfunction "6_6") (pintype "unspecified"))
      (node (ref "U10") (pin "16") (pinfunction "VCC_16") (pintype "unspecified"))
      (node (ref "U10") (pin "5") (pinfunction "U#/D_5") (pintype "unspecified"))
      (node (ref "U11") (pin "14") (pinfunction "VCC_14") (pintype "unspecified"))
      (node (ref "U12") (pin "14") (pinfunction "VCC_14") (pintype "unspecified"))
      (node (ref "U14") (pin "3") (pinfunction "3_3") (pintype "unspecified"))
      (node (ref "U15") (pin "3") (pinfunction "3_3") (pintype "unspecified"))
      (node (ref "U16") (pin "1") (pinfunction "CLR#_1") (pintype "unspecified"))
      (node (ref "U16") (pin "16") (pinfunction "VCC_16") (pintype "unspecified"))
      (node (ref "U17") (pin "2") (pinfunction "2_2") (pintype "unspecified"))
      (node (ref "U2") (pin "1") (pinfunction "CLR1_1") (pintype "unspecified"))
      (node (ref "U2") (pin "14") (pinfunction "VCC_14") (pintype "unspecified"))
      (node (ref "U2") (pin "4") (pinfunction "PR1_4") (pintype "unspecified"))
      (node (ref "U3") (pin "14") (pinfunction "VCC_14") (pintype "unspecified"))
      (node (ref "U4") (pin "16") (pinfunction "VDD_16") (pintype "unspecified"))
      (node (ref "U4") (pin "4") (pinfunction "BI#_4") (pintype "unspecified"))
      (node (ref "U4") (pin "5") (pinfunction "LE_5") (pintype "unspecified"))
      (node (ref "U5") (pin "1") (pinfunction "CLR#_1") (pintype "unspecified"))
      (node (ref "U5") (pin "16") (pinfunction "VCC_16") (pintype "unspecified"))
      (node (ref "U7") (pin "16") (pinfunction "VCC_16") (pintype "unspecified"))
      (node (ref "U7") (pin "5") (pinfunction "U#/D_5") (pintype "unspecified"))
      (node (ref "U8") (pin "14") (pinfunction "VCC_14") (pintype "unspecified"))
      (node (ref "U9") (pin "16") (pinfunction "VDD_16") (pintype "unspecified"))
      (node (ref "U9") (pin "4") (pinfunction "BI#_4") (pintype "unspecified"))
      (node (ref "U9") (pin "5") (pinfunction "LE_5") (pintype "unspecified"))
    )
    (net (code "74") (name "unconnected-(U5-A-Pad3)") (class "Default")
      (node (ref "U5") (pin "3") (pinfunction "A_3") (pintype "unspecified"))
    )
    (net (code "75") (name "unconnected-(U5-B-Pad4)") (class "Default")
      (node (ref "U5") (pin "4") (pinfunction "B_4") (pintype "unspecified"))
    )
    (net (code "76") (name "unconnected-(U5-C-Pad5)") (class "Default")
      (node (ref "U5") (pin "5") (pinfunction "C_5") (pintype "unspecified"))
    )
    (net (code "77") (name "unconnected-(U5-D-Pad6)") (class "Default")
      (node (ref "U5") (pin "6") (pinfunction "D_6") (pintype "unspecified"))
    )
    (net (code "78") (name "unconnected-(U7-CE#-Pad4)") (class "Default")
      (node (ref "U7") (pin "4") (pinfunction "CE#_4") (pintype "unspecified"))
    )
    (net (code "79") (name "unconnected-(U7-TC-Pad12)") (class "Default")
      (node (ref "U7") (pin "12") (pinfunction "TC_12") (pintype "unspecified"))
    )
    (net (code "80") (name "unconnected-(U10-CE#-Pad4)") (class "Default")
      (node (ref "U10") (pin "4") (pinfunction "CE#_4") (pintype "unspecified"))
    )
    (net (code "81") (name "unconnected-(U10-TC-Pad12)") (class "Default")
      (node (ref "U10") (pin "12") (pinfunction "TC_12") (pintype "unspecified"))
    )
    (net (code "82") (name "unconnected-(U16-A-Pad3)") (class "Default")
      (node (ref "U16") (pin "3") (pinfunction "A_3") (pintype "unspecified"))
    )
    (net (code "83") (name "unconnected-(U16-B-Pad4)") (class "Default")
      (node (ref "U16") (pin "4") (pinfunction "B_4") (pintype "unspecified"))
    )
    (net (code "84") (name "unconnected-(U16-C-Pad5)") (class "Default")
      (node (ref "U16") (pin "5") (pinfunction "C_5") (pintype "unspecified"))
    )
    (net (code "85") (name "unconnected-(U16-D-Pad6)") (class "Default")
      (node (ref "U16") (pin "6") (pinfunction "D_6") (pintype "unspecified"))
    )
  )
)
